# Ring_5_A.net
KiCad netlist of a schematic drawn in Altium Designer
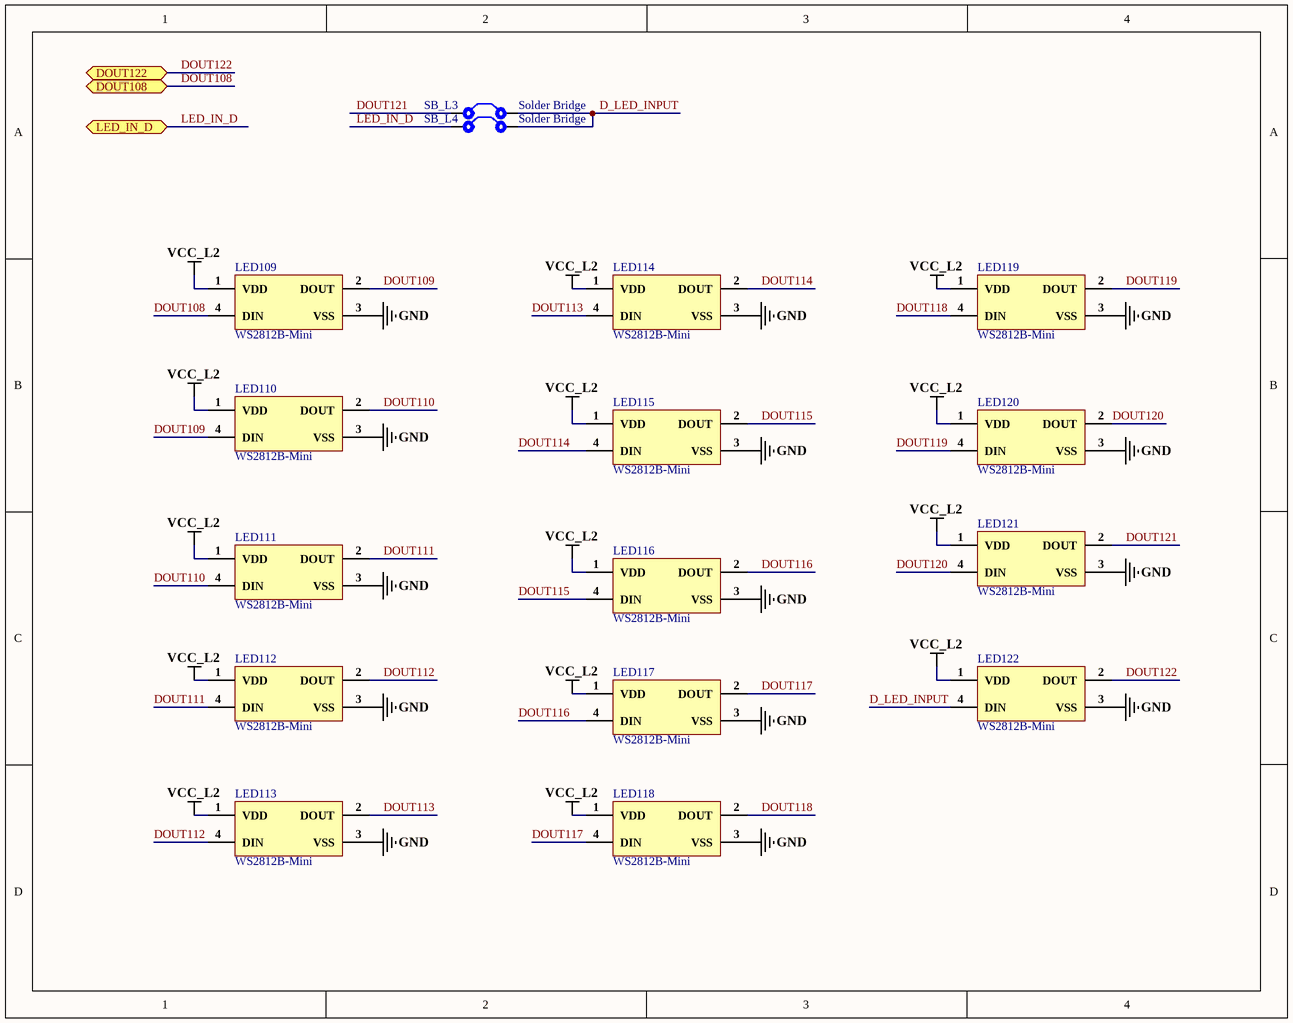
[diagram p0: Ring 5_A.SchDoc]

(export (version "E")
  (design (tool "Eeschema 10.0.6"))
  (components
    (comp (ref "LED109")
      (value "WS2812B-Mini")
      (footprint "WS2812B-Mini")
      (description "SMD,3.5x3.5mm Light Emitting Diodes (LED) RoHS")
      (fields (field (name "MANUFACTURER") "Worldsemi"))
      (libsource (lib "TT_IntLib") (part "WS2812B-Mini"))
    )
    (comp (ref "LED110")
      (value "WS2812B-Mini")
      (footprint "WS2812B-Mini")
      (description "SMD,3.5x3.5mm Light Emitting Diodes (LED) RoHS")
      (fields (field (name "MANUFACTURER") "Worldsemi"))
      (libsource (lib "TT_IntLib") (part "WS2812B-Mini"))
    )
    (comp (ref "LED111")
      (value "WS2812B-Mini")
      (footprint "WS2812B-Mini")
      (description "SMD,3.5x3.5mm Light Emitting Diodes (LED) RoHS")
      (fields (field (name "MANUFACTURER") "Worldsemi"))
      (libsource (lib "TT_IntLib") (part "WS2812B-Mini"))
    )
    (comp (ref "LED112")
      (value "WS2812B-Mini")
      (footprint "WS2812B-Mini")
      (description "SMD,3.5x3.5mm Light Emitting Diodes (LED) RoHS")
      (fields (field (name "MANUFACTURER") "Worldsemi"))
      (libsource (lib "TT_IntLib") (part "WS2812B-Mini"))
    )
    (comp (ref "LED113")
      (value "WS2812B-Mini")
      (footprint "WS2812B-Mini")
      (description "SMD,3.5x3.5mm Light Emitting Diodes (LED) RoHS")
      (fields (field (name "MANUFACTURER") "Worldsemi"))
      (libsource (lib "TT_IntLib") (part "WS2812B-Mini"))
    )
    (comp (ref "LED114")
      (value "WS2812B-Mini")
      (footprint "WS2812B-Mini")
      (description "SMD,3.5x3.5mm Light Emitting Diodes (LED) RoHS")
      (fields (field (name "MANUFACTURER") "Worldsemi"))
      (libsource (lib "TT_IntLib") (part "WS2812B-Mini"))
    )
    (comp (ref "LED115")
      (value "WS2812B-Mini")
      (footprint "WS2812B-Mini")
      (description "SMD,3.5x3.5mm Light Emitting Diodes (LED) RoHS")
      (fields (field (name "MANUFACTURER") "Worldsemi"))
      (libsource (lib "TT_IntLib") (part "WS2812B-Mini"))
    )
    (comp (ref "LED116")
      (value "WS2812B-Mini")
      (footprint "WS2812B-Mini")
      (description "SMD,3.5x3.5mm Light Emitting Diodes (LED) RoHS")
      (fields (field (name "MANUFACTURER") "Worldsemi"))
      (libsource (lib "TT_IntLib") (part "WS2812B-Mini"))
    )
    (comp (ref "LED117")
      (value "WS2812B-Mini")
      (footprint "WS2812B-Mini")
      (description "SMD,3.5x3.5mm Light Emitting Diodes (LED) RoHS")
      (fields (field (name "MANUFACTURER") "Worldsemi"))
      (libsource (lib "TT_IntLib") (part "WS2812B-Mini"))
    )
    (comp (ref "LED118")
      (value "WS2812B-Mini")
      (footprint "WS2812B-Mini")
      (description "SMD,3.5x3.5mm Light Emitting Diodes (LED) RoHS")
      (fields (field (name "MANUFACTURER") "Worldsemi"))
      (libsource (lib "TT_IntLib") (part "WS2812B-Mini"))
    )
    (comp (ref "LED119")
      (value "WS2812B-Mini")
      (footprint "WS2812B-Mini")
      (description "SMD,3.5x3.5mm Light Emitting Diodes (LED) RoHS")
      (fields (field (name "MANUFACTURER") "Worldsemi"))
      (libsource (lib "TT_IntLib") (part "WS2812B-Mini"))
    )
    (comp (ref "LED120")
      (value "WS2812B-Mini")
      (footprint "WS2812B-Mini")
      (description "SMD,3.5x3.5mm Light Emitting Diodes (LED) RoHS")
      (fields (field (name "MANUFACTURER") "Worldsemi"))
      (libsource (lib "TT_IntLib") (part "WS2812B-Mini"))
    )
    (comp (ref "LED121")
      (value "WS2812B-Mini")
      (footprint "WS2812B-Mini")
      (description "SMD,3.5x3.5mm Light Emitting Diodes (LED) RoHS")
      (fields (field (name "MANUFACTURER") "Worldsemi"))
      (libsource (lib "TT_IntLib") (part "WS2812B-Mini"))
    )
    (comp (ref "LED122")
      (value "WS2812B-Mini")
      (footprint "WS2812B-Mini")
      (description "SMD,3.5x3.5mm Light Emitting Diodes (LED) RoHS")
      (fields (field (name "MANUFACTURER") "Worldsemi"))
      (libsource (lib "TT_IntLib") (part "WS2812B-Mini"))
    )
    (comp (ref "SB_L3")
      (value "Solder Bridge")
      (footprint "Solder Bridge")
      (description "Solder Bridge ON")
      (libsource (lib "TT_IntLib") (part "Solder Bridge"))
    )
    (comp (ref "SB_L4")
      (value "Solder Bridge")
      (footprint "Solder Bridge")
      (description "Solder Bridge ON")
      (libsource (lib "TT_IntLib") (part "Solder Bridge"))
    )
  )
  (nets
    (net (code "1") (name "/DOUT108") (class "Default")
      (node (ref "LED109") (pin "4") (pinfunction "DIN_4") (pintype "passive"))
    )
    (net (code "2") (name "/DOUT109") (class "Default")
      (node (ref "LED109") (pin "2") (pinfunction "DOUT_2") (pintype "passive"))
      (node (ref "LED110") (pin "4") (pinfunction "DIN_4") (pintype "passive"))
    )
    (net (code "3") (name "/DOUT110") (class "Default")
      (node (ref "LED110") (pin "2") (pinfunction "DOUT_2") (pintype "passive"))
      (node (ref "LED111") (pin "4") (pinfunction "DIN_4") (pintype "passive"))
    )
    (net (code "4") (name "/DOUT111") (class "Default")
      (node (ref "LED111") (pin "2") (pinfunction "DOUT_2") (pintype "passive"))
      (node (ref "LED112") (pin "4") (pinfunction "DIN_4") (pintype "passive"))
    )
    (net (code "5") (name "/DOUT112") (class "Default")
      (node (ref "LED112") (pin "2") (pinfunction "DOUT_2") (pintype "passive"))
      (node (ref "LED113") (pin "4") (pinfunction "DIN_4") (pintype "passive"))
    )
    (net (code "6") (name "/DOUT113") (class "Default")
      (node (ref "LED113") (pin "2") (pinfunction "DOUT_2") (pintype "passive"))
      (node (ref "LED114") (pin "4") (pinfunction "DIN_4") (pintype "passive"))
    )
    (net (code "7") (name "/DOUT114") (class "Default")
      (node (ref "LED114") (pin "2") (pinfunction "DOUT_2") (pintype "passive"))
      (node (ref "LED115") (pin "4") (pinfunction "DIN_4") (pintype "passive"))
    )
    (net (code "8") (name "/DOUT115") (class "Default")
      (node (ref "LED115") (pin "2") (pinfunction "DOUT_2") (pintype "passive"))
      (node (ref "LED116") (pin "4") (pinfunction "DIN_4") (pintype "passive"))
    )
    (net (code "9") (name "/DOUT116") (class "Default")
      (node (ref "LED116") (pin "2") (pinfunction "DOUT_2") (pintype "passive"))
      (node (ref "LED117") (pin "4") (pinfunction "DIN_4") (pintype "passive"))
    )
    (net (code "10") (name "/DOUT117") (class "Default")
      (node (ref "LED117") (pin "2") (pinfunction "DOUT_2") (pintype "passive"))
      (node (ref "LED118") (pin "4") (pinfunction "DIN_4") (pintype "passive"))
    )
    (net (code "11") (name "/DOUT118") (class "Default")
      (node (ref "LED118") (pin "2") (pinfunction "DOUT_2") (pintype "passive"))
      (node (ref "LED119") (pin "4") (pinfunction "DIN_4") (pintype "passive"))
    )
    (net (code "12") (name "/DOUT119") (class "Default")
      (node (ref "LED119") (pin "2") (pinfunction "DOUT_2") (pintype "passive"))
      (node (ref "LED120") (pin "4") (pinfunction "DIN_4") (pintype "passive"))
    )
    (net (code "13") (name "/DOUT120") (class "Default")
      (node (ref "LED120") (pin "2") (pinfunction "DOUT_2") (pintype "passive"))
      (node (ref "LED121") (pin "4") (pinfunction "DIN_4") (pintype "passive"))
    )
    (net (code "14") (name "/DOUT121") (class "Default")
      (node (ref "LED121") (pin "2") (pinfunction "DOUT_2") (pintype "passive"))
      (node (ref "SB_L3") (pin "1") (pinfunction "1_1") (pintype "passive"))
    )
    (net (code "15") (name "/DOUT122") (class "Default")
      (node (ref "LED122") (pin "2") (pinfunction "DOUT_2") (pintype "passive"))
    )
    (net (code "16") (name "/D_LED_INPUT") (class "Default")
      (node (ref "LED122") (pin "4") (pinfunction "DIN_4") (pintype "passive"))
      (node (ref "SB_L3") (pin "2") (pinfunction "2_2") (pintype "passive"))
      (node (ref "SB_L4") (pin "2") (pinfunction "2_2") (pintype "passive"))
    )
    (net (code "17") (name "/LED_IN_D") (class "Default")
      (node (ref "SB_L4") (pin "1") (pinfunction "1_1") (pintype "passive"))
    )
    (net (code "18") (name "GND") (class "Default")
      (node (ref "LED109") (pin "3") (pinfunction "VSS_3") (pintype "passive"))
      (node (ref "LED110") (pin "3") (pinfunction "VSS_3") (pintype "passive"))
      (node (ref "LED111") (pin "3") (pinfunction "VSS_3") (pintype "passive"))
      (node (ref "LED112") (pin "3") (pinfunction "VSS_3") (pintype "passive"))
      (node (ref "LED113") (pin "3") (pinfunction "VSS_3") (pintype "passive"))
      (node (ref "LED114") (pin "3") (pinfunction "VSS_3") (pintype "passive"))
      (node (ref "LED115") (pin "3") (pinfunction "VSS_3") (pintype "passive"))
      (node (ref "LED116") (pin "3") (pinfunction "VSS_3") (pintype "passive"))
      (node (ref "LED117") (pin "3") (pinfunction "VSS_3") (pintype "passive"))
      (node (ref "LED118") (pin "3") (pinfunction "VSS_3") (pintype "passive"))
      (node (ref "LED119") (pin "3") (pinfunction "VSS_3") (pintype "passive"))
      (node (ref "LED120") (pin "3") (pinfunction "VSS_3") (pintype "passive"))
      (node (ref "LED121") (pin "3") (pinfunction "VSS_3") (pintype "passive"))
      (node (ref "LED122") (pin "3") (pinfunction "VSS_3") (pintype "passive"))
    )
    (net (code "19") (name "VCC_L2") (class "Default")
      (node (ref "LED109") (pin "1") (pinfunction "VDD_1") (pintype "passive"))
      (node (ref "LED110") (pin "1") (pinfunction "VDD_1") (pintype "passive"))
      (node (ref "LED111") (pin "1") (pinfunction "VDD_1") (pintype "passive"))
      (node (ref "LED112") (pin "1") (pinfunction "VDD_1") (pintype "passive"))
      (node (ref "LED113") (pin "1") (pinfunction "VDD_1") (pintype "passive"))
      (node (ref "LED114") (pin "1") (pinfunction "VDD_1") (pintype "passive"))
      (node (ref "LED115") (pin "1") (pinfunction "VDD_1") (pintype "passive"))
      (node (ref "LED116") (pin "1") (pinfunction "VDD_1") (pintype "passive"))
      (node (ref "LED117") (pin "1") (pinfunction "VDD_1") (pintype "passive"))
      (node (ref "LED118") (pin "1") (pinfunction "VDD_1") (pintype "passive"))
      (node (ref "LED119") (pin "1") (pinfunction "VDD_1") (pintype "passive"))
      (node (ref "LED120") (pin "1") (pinfunction "VDD_1") (pintype "passive"))
      (node (ref "LED121") (pin "1") (pinfunction "VDD_1") (pintype "passive"))
      (node (ref "LED122") (pin "1") (pinfunction "VDD_1") (pintype "passive"))
    )
  )
)
